# placaAindanFinalizada.net
KiCad netlist of a schematic drawn in EAGLE
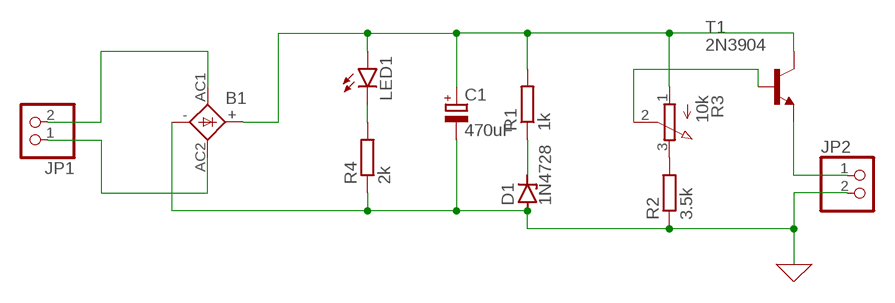
[diagram p0: schematic, sheet 1]

(export (version "E")
  (design (tool "Eeschema 10.0.6"))
  (components
    (comp (ref "B1")
      (value "1KAB")
      (footprint "eagle-import:1KAB")
      (libsource (lib "eagle-import") (part "1KAB"))
    )
    (comp (ref "C1")
      (value "470uF")
      (footprint "eagle-import:E5-10,5")
      (libsource (lib "eagle-import") (part "CPOL-EUE5-10.5"))
    )
    (comp (ref "D1")
      (value "1N4728")
      (footprint "eagle-import:DO41Z10")
      (libsource (lib "eagle-import") (part "1N4728"))
    )
    (comp (ref "JP1")
      (value "PINHD-1X2")
      (footprint "eagle-import:1X02")
      (libsource (lib "eagle-import") (part "PINHD-1X2"))
    )
    (comp (ref "JP2")
      (value "PINHD-1X2")
      (footprint "eagle-import:1X02")
      (libsource (lib "eagle-import") (part "PINHD-1X2"))
    )
    (comp (ref "LED1")
      (value "LED5MM")
      (footprint "eagle-import:LED5MM")
      (libsource (lib "eagle-import") (part "LED5MM"))
    )
    (comp (ref "R1")
      (value "1k")
      (footprint "eagle-import:0204_7")
      (libsource (lib "eagle-import") (part "R-EU_0204/7"))
    )
    (comp (ref "R2")
      (value "3.5k")
      (footprint "eagle-import:0204_7")
      (libsource (lib "eagle-import") (part "R-EU_0204/7"))
    )
    (comp (ref "R3")
      (value "10k")
      (footprint "eagle-import:3RP_1610N")
      (libsource (lib "eagle-import") (part "3RP/1610N"))
    )
    (comp (ref "R4")
      (value "2k")
      (footprint "eagle-import:0204_7")
      (libsource (lib "eagle-import") (part "R-EU_0204/7"))
    )
    (comp (ref "T1")
      (value "2N3904")
      (footprint "eagle-import:TO92")
      (libsource (lib "eagle-import") (part "2N3904"))
    )
  )
  (nets
    (net (code "1") (name "GND") (class "Default")
      (node (ref "B1") (pin "-") (pinfunction "-_-") (pintype "passive"))
      (node (ref "C1") (pin "-") (pinfunction "-_-") (pintype "passive"))
      (node (ref "D1") (pin "A") (pinfunction "A_A") (pintype "passive"))
      (node (ref "JP2") (pin "2") (pinfunction "2_2") (pintype "passive"))
      (node (ref "R2") (pin "1") (pinfunction "1_1") (pintype "passive"))
      (node (ref "R4") (pin "1") (pinfunction "1_1") (pintype "passive"))
    )
    (net (code "2") (name "Net-(B1-PadAC1)") (class "Default")
      (node (ref "B1") (pin "AC1") (pinfunction "AC1_AC1") (pintype "passive"))
      (node (ref "JP1") (pin "2") (pinfunction "2_2") (pintype "passive"))
    )
    (net (code "3") (name "Net-(B1-PadAC2)") (class "Default")
      (node (ref "B1") (pin "AC2") (pinfunction "AC2_AC2") (pintype "passive"))
      (node (ref "JP1") (pin "1") (pinfunction "1_1") (pintype "passive"))
    )
    (net (code "4") (name "Net-(D1-PadC)") (class "Default")
      (node (ref "D1") (pin "C") (pinfunction "C_C") (pintype "passive"))
      (node (ref "R1") (pin "1") (pinfunction "1_1") (pintype "passive"))
    )
    (net (code "5") (name "Net-(LED1-C)") (class "Default")
      (node (ref "LED1") (pin "K") (pinfunction "C_K") (pintype "passive"))
      (node (ref "R4") (pin "2") (pinfunction "2_2") (pintype "passive"))
    )
    (net (code "6") (name "Net-(R3-A)") (class "Default")
      (node (ref "B1") (pin "+") (pinfunction "+_+") (pintype "passive"))
      (node (ref "C1") (pin "+") (pinfunction "+_+") (pintype "passive"))
      (node (ref "LED1") (pin "A") (pinfunction "A_A") (pintype "passive"))
      (node (ref "R1") (pin "2") (pinfunction "2_2") (pintype "passive"))
      (node (ref "R3") (pin "1") (pinfunction "A_1") (pintype "passive"))
      (node (ref "T1") (pin "1") (pinfunction "C_1") (pintype "passive"))
    )
    (net (code "7") (name "Net-(R3-E)") (class "Default")
      (node (ref "R2") (pin "2") (pinfunction "2_2") (pintype "passive"))
      (node (ref "R3") (pin "3") (pinfunction "E_3") (pintype "passive"))
    )
    (net (code "8") (name "Net-(R3-S)") (class "Default")
      (node (ref "R3") (pin "2") (pinfunction "S_2") (pintype "passive"))
      (node (ref "T1") (pin "2") (pinfunction "B_2") (pintype "passive"))
    )
    (net (code "9") (name "Net-(T1-E)") (class "Default")
      (node (ref "JP2") (pin "1") (pinfunction "1_1") (pintype "passive"))
      (node (ref "T1") (pin "3") (pinfunction "E_3") (pintype "passive"))
    )
  )
)
